# IDC_SMA_Adapter.net
KiCad netlist of a schematic drawn in Altium Designer
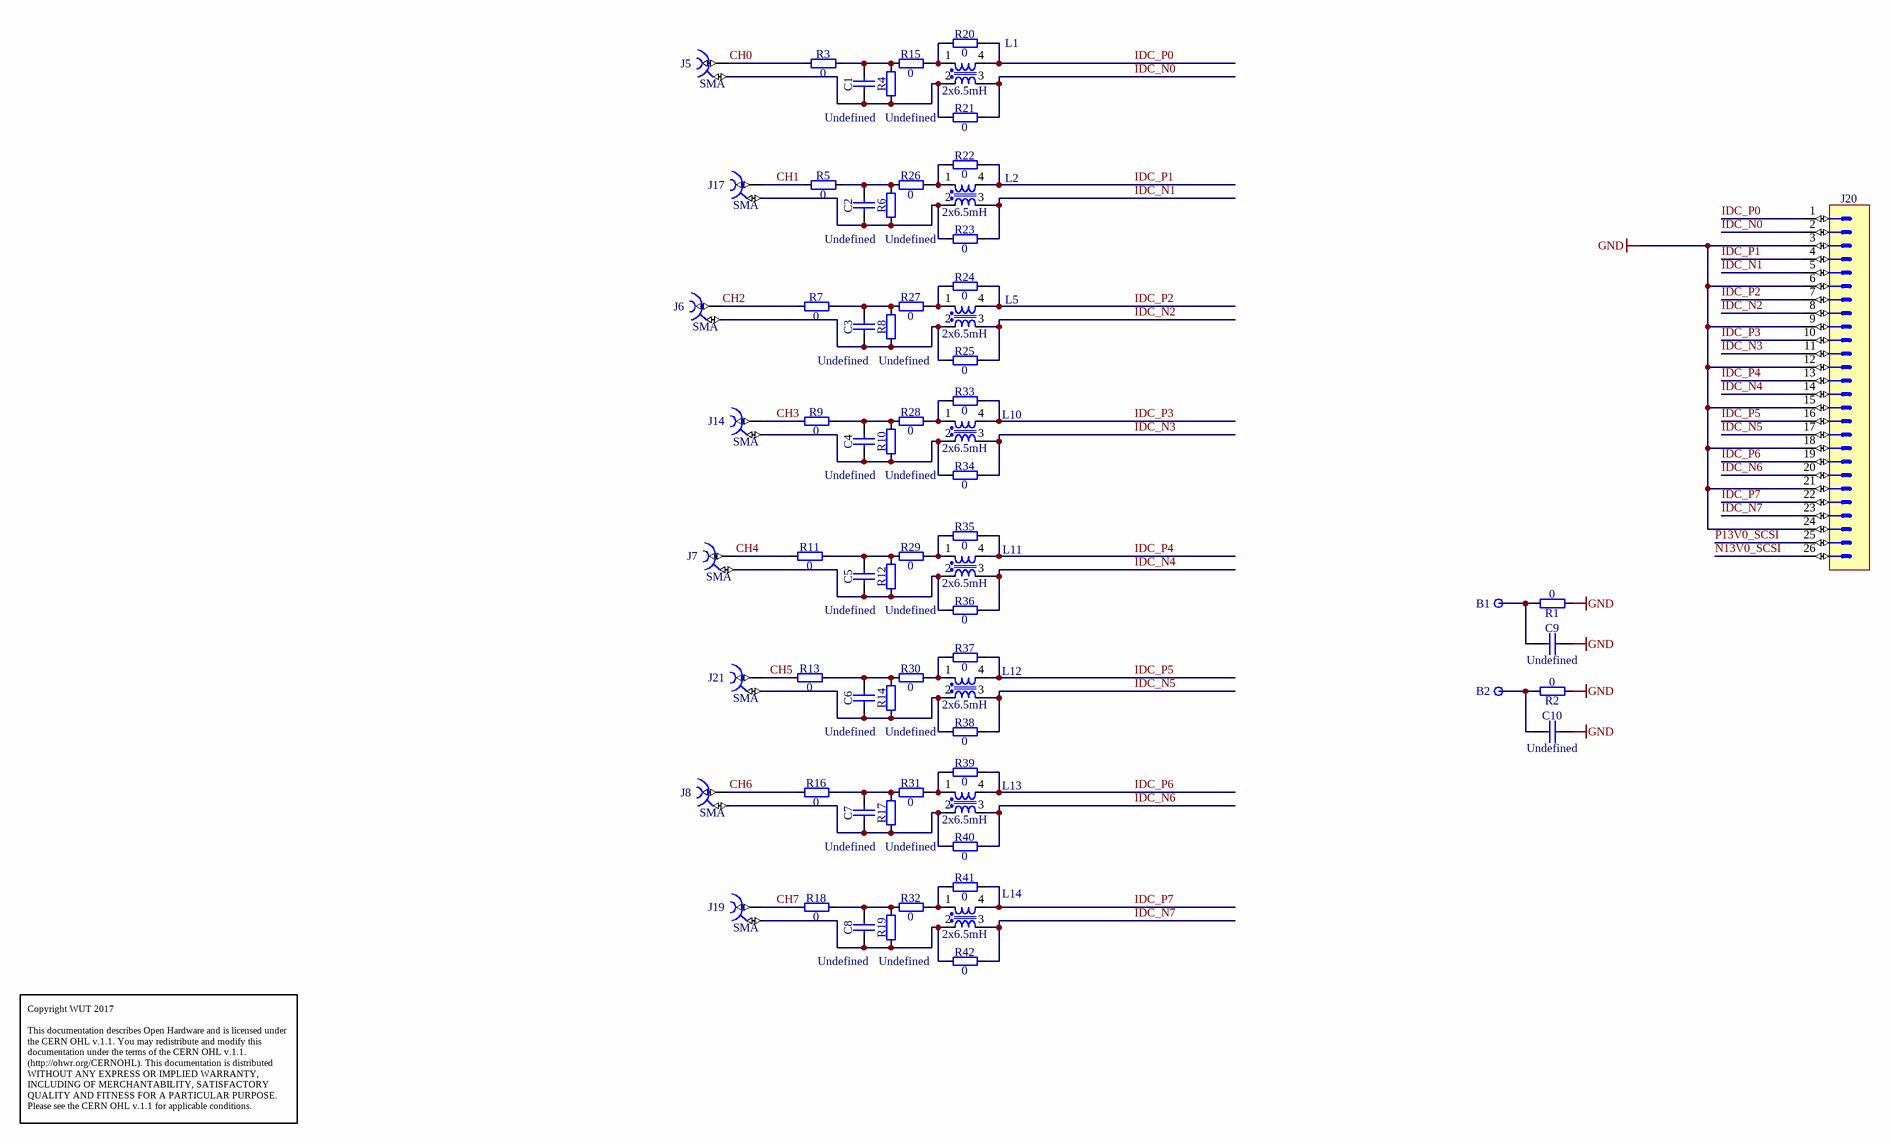
[diagram p0: IDC_SMA_Adapter.SchDoc]

(export (version "E")
  (design (tool "Eeschema 10.0.6"))
  (components
    (comp (ref "B1")
      (value "Plated Hole")
      (footprint "MTG270_500")
      (description "Single Terminal Socket")
      (fields (field (name "PART NUMBER") "PLATED_HOLE2.7_PAD5.0") (field (name "AUTHOR") "CERN DEM JMW"))
      (libsource (lib "Eletro-mechanical") (part "Single Terminal Socket"))
    )
    (comp (ref "B2")
      (value "Plated Hole")
      (footprint "MTG270_500")
      (description "Single Terminal Socket")
      (fields (field (name "PART NUMBER") "PLATED_HOLE2.7_PAD5.0") (field (name "AUTHOR") "CERN DEM JMW"))
      (libsource (lib "Eletro-mechanical") (part "Single Terminal Socket"))
    )
    (comp (ref "C1")
      (value "Undefined")
      (footprint "CAPC2012X135N")
      (description "Non-polarised capacitor")
      (fields (field (name "PART NUMBER") "CC0805_NO-VALUE") (field (name "AUTHOR") "CERN DEM JLC"))
      (libsource (lib "Capacitors") (part "Capacitor - non polarized"))
    )
    (comp (ref "C2")
      (value "Undefined")
      (footprint "CAPC2012X135N")
      (description "Non-polarised capacitor")
      (fields (field (name "PART NUMBER") "CC0805_NO-VALUE") (field (name "AUTHOR") "CERN DEM JLC"))
      (libsource (lib "Capacitors") (part "Capacitor - non polarized"))
    )
    (comp (ref "C3")
      (value "Undefined")
      (footprint "CAPC2012X135N")
      (description "Non-polarised capacitor")
      (fields (field (name "PART NUMBER") "CC0805_NO-VALUE") (field (name "AUTHOR") "CERN DEM JLC"))
      (libsource (lib "Capacitors") (part "Capacitor - non polarized"))
    )
    (comp (ref "C4")
      (value "Undefined")
      (footprint "CAPC2012X135N")
      (description "Non-polarised capacitor")
      (fields (field (name "PART NUMBER") "CC0805_NO-VALUE") (field (name "AUTHOR") "CERN DEM JLC"))
      (libsource (lib "Capacitors") (part "Capacitor - non polarized"))
    )
    (comp (ref "C5")
      (value "Undefined")
      (footprint "CAPC2012X135N")
      (description "Non-polarised capacitor")
      (fields (field (name "PART NUMBER") "CC0805_NO-VALUE") (field (name "AUTHOR") "CERN DEM JLC"))
      (libsource (lib "Capacitors") (part "Capacitor - non polarized"))
    )
    (comp (ref "C6")
      (value "Undefined")
      (footprint "CAPC2012X135N")
      (description "Non-polarised capacitor")
      (fields (field (name "PART NUMBER") "CC0805_NO-VALUE") (field (name "AUTHOR") "CERN DEM JLC"))
      (libsource (lib "Capacitors") (part "Capacitor - non polarized"))
    )
    (comp (ref "C7")
      (value "Undefined")
      (footprint "CAPC2012X135N")
      (description "Non-polarised capacitor")
      (fields (field (name "PART NUMBER") "CC0805_NO-VALUE") (field (name "AUTHOR") "CERN DEM JLC"))
      (libsource (lib "Capacitors") (part "Capacitor - non polarized"))
    )
    (comp (ref "C8")
      (value "Undefined")
      (footprint "CAPC2012X135N")
      (description "Non-polarised capacitor")
      (fields (field (name "PART NUMBER") "CC0805_NO-VALUE") (field (name "AUTHOR") "CERN DEM JLC"))
      (libsource (lib "Capacitors") (part "Capacitor - non polarized"))
    )
    (comp (ref "C9")
      (value "Undefined")
      (footprint "CAPC2012X135N")
      (description "Non-polarised capacitor")
      (fields (field (name "PART NUMBER") "CC0805_NO-VALUE") (field (name "AUTHOR") "CERN DEM JLC"))
      (libsource (lib "Capacitors") (part "Capacitor - non polarized"))
    )
    (comp (ref "C10")
      (value "Undefined")
      (footprint "CAPC2012X135N")
      (description "Non-polarised capacitor")
      (fields (field (name "PART NUMBER") "CC0805_NO-VALUE") (field (name "AUTHOR") "CERN DEM JLC"))
      (libsource (lib "Capacitors") (part "Capacitor - non polarized"))
    )
    (comp (ref "J5")
      (value "SMA")
      (footprint "DELOCK_65848")
      (description "50 Ohm Through Hole SMA Right Angle PCB Jack")
      (fields
        (field (name "PART NUMBER") "DELOCK_65848")
        (field (name "MANUFACTURER") "DELOCK")
        (field (name "AUTHOR") "GK")
      )
      (libsource (lib "Connectors") (part "CON_SMA_DELOCK_65848"))
    )
    (comp (ref "J6")
      (value "SMA")
      (footprint "DELOCK_65848")
      (description "50 Ohm Through Hole SMA Right Angle PCB Jack")
      (fields
        (field (name "PART NUMBER") "DELOCK_65848")
        (field (name "MANUFACTURER") "DELOCK")
        (field (name "AUTHOR") "GK")
      )
      (libsource (lib "Connectors") (part "CON_SMA_DELOCK_65848"))
    )
    (comp (ref "J7")
      (value "SMA")
      (footprint "DELOCK_65848")
      (description "50 Ohm Through Hole SMA Right Angle PCB Jack")
      (fields
        (field (name "PART NUMBER") "DELOCK_65848")
        (field (name "MANUFACTURER") "DELOCK")
        (field (name "AUTHOR") "GK")
      )
      (libsource (lib "Connectors") (part "CON_SMA_DELOCK_65848"))
    )
    (comp (ref "J8")
      (value "SMA")
      (footprint "DELOCK_65848")
      (description "50 Ohm Through Hole SMA Right Angle PCB Jack")
      (fields
        (field (name "PART NUMBER") "DELOCK_65848")
        (field (name "MANUFACTURER") "DELOCK")
        (field (name "AUTHOR") "GK")
      )
      (libsource (lib "Connectors") (part "CON_SMA_DELOCK_65848"))
    )
    (comp (ref "J14")
      (value "SMA")
      (footprint "MOLEX_73251-2120")
      (description "50 Ohm, SMA Edge Mount PCB, With Jam Nut And Lock Washer")
      (fields
        (field (name "PART NUMBER") "MOLEX_73251-2120")
        (field (name "MANUFACTURER") "MOLEX")
        (field (name "AUTHOR") "CERN DEM JLC")
      )
      (libsource (lib "LIBRARY_SCH") (part "CON_SMA_RA_SMD_73251-2120"))
    )
    (comp (ref "J17")
      (value "SMA")
      (footprint "MOLEX_73251-2120")
      (description "50 Ohm, SMA Edge Mount PCB, With Jam Nut And Lock Washer")
      (fields
        (field (name "PART NUMBER") "MOLEX_73251-2120")
        (field (name "MANUFACTURER") "MOLEX")
        (field (name "AUTHOR") "CERN DEM JLC")
      )
      (libsource (lib "LIBRARY_SCH") (part "CON_SMA_RA_SMD_73251-2120"))
    )
    (comp (ref "J19")
      (value "SMA")
      (footprint "MOLEX_73251-2120")
      (description "50 Ohm, SMA Edge Mount PCB, With Jam Nut And Lock Washer")
      (fields
        (field (name "PART NUMBER") "MOLEX_73251-2120")
        (field (name "MANUFACTURER") "MOLEX")
        (field (name "AUTHOR") "CERN DEM JLC")
      )
      (libsource (lib "LIBRARY_SCH") (part "CON_SMA_RA_SMD_73251-2120"))
    )
    (comp (ref "J20")
      (value "Header 26")
      (footprint "3M_N2526-6003RB")
      (description "Connector 26 Male")
      (fields
        (field (name "PART NUMBER") "3M_N2526-6003RB")
        (field (name "MANUFACTURER") "3M")
        (field (name "AUTHOR") "CERN DEM JLC")
      )
      (libsource (lib "Connectors") (part "Connector 26 Male"))
    )
    (comp (ref "J21")
      (value "SMA")
      (footprint "MOLEX_73251-2120")
      (description "50 Ohm, SMA Edge Mount PCB, With Jam Nut And Lock Washer")
      (fields
        (field (name "PART NUMBER") "MOLEX_73251-2120")
        (field (name "MANUFACTURER") "MOLEX")
        (field (name "AUTHOR") "CERN DEM JLC")
      )
      (libsource (lib "LIBRARY_SCH") (part "CON_SMA_RA_SMD_73251-2120"))
    )
    (comp (ref "L1")
      (value "2x6.5mH")
      (footprint "IND_WURTH_WE-SL2")
      (description "Inductor Common Mode")
      (fields
        (field (name "PART NUMBER") "IND_6.5MH_50%_WURTH_WE-SL2-744229")
        (field (name "POWER") "400mA")
        (field (name "AUTHOR") "CERN DEM JLC")
      )
      (libsource (lib "Inductors & Transformers") (part "Inductor Common Mode 1Dot-4 2Dot-3"))
    )
    (comp (ref "L2")
      (value "2x6.5mH")
      (footprint "IND_WURTH_WE-SL2")
      (description "Inductor Common Mode")
      (fields
        (field (name "PART NUMBER") "IND_6.5MH_50%_WURTH_WE-SL2-744229")
        (field (name "POWER") "400mA")
        (field (name "AUTHOR") "CERN DEM JLC")
      )
      (libsource (lib "Inductors & Transformers") (part "Inductor Common Mode 1Dot-4 2Dot-3"))
    )
    (comp (ref "L5")
      (value "2x6.5mH")
      (footprint "IND_WURTH_WE-SL2")
      (description "Inductor Common Mode")
      (fields
        (field (name "PART NUMBER") "IND_6.5MH_50%_WURTH_WE-SL2-744229")
        (field (name "POWER") "400mA")
        (field (name "AUTHOR") "CERN DEM JLC")
      )
      (libsource (lib "Inductors & Transformers") (part "Inductor Common Mode 1Dot-4 2Dot-3"))
    )
    (comp (ref "L10")
      (value "2x6.5mH")
      (footprint "IND_WURTH_WE-SL2")
      (description "Inductor Common Mode")
      (fields
        (field (name "PART NUMBER") "IND_6.5MH_50%_WURTH_WE-SL2-744229")
        (field (name "POWER") "400mA")
        (field (name "AUTHOR") "CERN DEM JLC")
      )
      (libsource (lib "Inductors & Transformers") (part "Inductor Common Mode 1Dot-4 2Dot-3"))
    )
    (comp (ref "L11")
      (value "2x6.5mH")
      (footprint "IND_WURTH_WE-SL2")
      (description "Inductor Common Mode")
      (fields
        (field (name "PART NUMBER") "IND_6.5MH_50%_WURTH_WE-SL2-744229")
        (field (name "POWER") "400mA")
        (field (name "AUTHOR") "CERN DEM JLC")
      )
      (libsource (lib "Inductors & Transformers") (part "Inductor Common Mode 1Dot-4 2Dot-3"))
    )
    (comp (ref "L12")
      (value "2x6.5mH")
      (footprint "IND_WURTH_WE-SL2")
      (description "Inductor Common Mode")
      (fields
        (field (name "PART NUMBER") "IND_6.5MH_50%_WURTH_WE-SL2-744229")
        (field (name "POWER") "400mA")
        (field (name "AUTHOR") "CERN DEM JLC")
      )
      (libsource (lib "Inductors & Transformers") (part "Inductor Common Mode 1Dot-4 2Dot-3"))
    )
    (comp (ref "L13")
      (value "2x6.5mH")
      (footprint "IND_WURTH_WE-SL2")
      (description "Inductor Common Mode")
      (fields
        (field (name "PART NUMBER") "IND_6.5MH_50%_WURTH_WE-SL2-744229")
        (field (name "POWER") "400mA")
        (field (name "AUTHOR") "CERN DEM JLC")
      )
      (libsource (lib "Inductors & Transformers") (part "Inductor Common Mode 1Dot-4 2Dot-3"))
    )
    (comp (ref "L14")
      (value "2x6.5mH")
      (footprint "IND_WURTH_WE-SL2")
      (description "Inductor Common Mode")
      (fields
        (field (name "PART NUMBER") "IND_6.5MH_50%_WURTH_WE-SL2-744229")
        (field (name "POWER") "400mA")
        (field (name "AUTHOR") "CERN DEM JLC")
      )
      (libsource (lib "Inductors & Transformers") (part "Inductor Common Mode 1Dot-4 2Dot-3"))
    )
    (comp (ref "R1")
      (value "0")
      (footprint "RESC1608X55N")
      (description "Resistor")
      (fields
        (field (name "PART NUMBER") "R0603_0R_JUMPER")
        (field (name "MANUFACTURER") "GENERIC")
        (field (name "AUTHOR") "CERN DEM JLC")
      )
      (libsource (lib "Resistors") (part "Resistor"))
    )
    (comp (ref "R2")
      (value "0")
      (footprint "RESC1608X55N")
      (description "Resistor")
      (fields
        (field (name "PART NUMBER") "R0603_0R_JUMPER")
        (field (name "MANUFACTURER") "GENERIC")
        (field (name "AUTHOR") "CERN DEM JLC")
      )
      (libsource (lib "Resistors") (part "Resistor"))
    )
    (comp (ref "R3")
      (value "0")
      (footprint "RESC1608X55N")
      (description "Resistor")
      (fields
        (field (name "PART NUMBER") "R0603_0R_JUMPER")
        (field (name "MANUFACTURER") "GENERIC")
        (field (name "AUTHOR") "CERN DEM JLC")
      )
      (libsource (lib "Resistors") (part "Resistor"))
    )
    (comp (ref "R4")
      (value "Undefined")
      (footprint "RESC1608X55N")
      (description "Resistor")
      (fields (field (name "PART NUMBER") "R0603_NO-VALUE") (field (name "AUTHOR") "CERN DEM JLC"))
      (libsource (lib "Resistors") (part "Resistor"))
    )
    (comp (ref "R5")
      (value "0")
      (footprint "RESC1608X55N")
      (description "Resistor")
      (fields
        (field (name "PART NUMBER") "R0603_0R_JUMPER")
        (field (name "MANUFACTURER") "GENERIC")
        (field (name "AUTHOR") "CERN DEM JLC")
      )
      (libsource (lib "Resistors") (part "Resistor"))
    )
    (comp (ref "R6")
      (value "Undefined")
      (footprint "RESC1608X55N")
      (description "Resistor")
      (fields (field (name "PART NUMBER") "R0603_NO-VALUE") (field (name "AUTHOR") "CERN DEM JLC"))
      (libsource (lib "Resistors") (part "Resistor"))
    )
    (comp (ref "R7")
      (value "0")
      (footprint "RESC1608X55N")
      (description "Resistor")
      (fields
        (field (name "PART NUMBER") "R0603_0R_JUMPER")
        (field (name "MANUFACTURER") "GENERIC")
        (field (name "AUTHOR") "CERN DEM JLC")
      )
      (libsource (lib "Resistors") (part "Resistor"))
    )
    (comp (ref "R8")
      (value "Undefined")
      (footprint "RESC1608X55N")
      (description "Resistor")
      (fields (field (name "PART NUMBER") "R0603_NO-VALUE") (field (name "AUTHOR") "CERN DEM JLC"))
      (libsource (lib "Resistors") (part "Resistor"))
    )
    (comp (ref "R9")
      (value "0")
      (footprint "RESC1608X55N")
      (description "Resistor")
      (fields
        (field (name "PART NUMBER") "R0603_0R_JUMPER")
        (field (name "MANUFACTURER") "GENERIC")
        (field (name "AUTHOR") "CERN DEM JLC")
      )
      (libsource (lib "Resistors") (part "Resistor"))
    )
    (comp (ref "R10")
      (value "Undefined")
      (footprint "RESC1608X55N")
      (description "Resistor")
      (fields (field (name "PART NUMBER") "R0603_NO-VALUE") (field (name "AUTHOR") "CERN DEM JLC"))
      (libsource (lib "Resistors") (part "Resistor"))
    )
    (comp (ref "R11")
      (value "0")
      (footprint "RESC1608X55N")
      (description "Resistor")
      (fields
        (field (name "PART NUMBER") "R0603_0R_JUMPER")
        (field (name "MANUFACTURER") "GENERIC")
        (field (name "AUTHOR") "CERN DEM JLC")
      )
      (libsource (lib "Resistors") (part "Resistor"))
    )
    (comp (ref "R12")
      (value "Undefined")
      (footprint "RESC1608X55N")
      (description "Resistor")
      (fields (field (name "PART NUMBER") "R0603_NO-VALUE") (field (name "AUTHOR") "CERN DEM JLC"))
      (libsource (lib "Resistors") (part "Resistor"))
    )
    (comp (ref "R13")
      (value "0")
      (footprint "RESC1608X55N")
      (description "Resistor")
      (fields
        (field (name "PART NUMBER") "R0603_0R_JUMPER")
        (field (name "MANUFACTURER") "GENERIC")
        (field (name "AUTHOR") "CERN DEM JLC")
      )
      (libsource (lib "Resistors") (part "Resistor"))
    )
    (comp (ref "R14")
      (value "Undefined")
      (footprint "RESC1608X55N")
      (description "Resistor")
      (fields (field (name "PART NUMBER") "R0603_NO-VALUE") (field (name "AUTHOR") "CERN DEM JLC"))
      (libsource (lib "Resistors") (part "Resistor"))
    )
    (comp (ref "R15")
      (value "0")
      (footprint "RESC1608X55N")
      (description "Resistor")
      (fields
        (field (name "PART NUMBER") "R0603_0R_JUMPER")
        (field (name "MANUFACTURER") "GENERIC")
        (field (name "AUTHOR") "CERN DEM JLC")
      )
      (libsource (lib "Resistors") (part "Resistor"))
    )
    (comp (ref "R16")
      (value "0")
      (footprint "RESC1608X55N")
      (description "Resistor")
      (fields
        (field (name "PART NUMBER") "R0603_0R_JUMPER")
        (field (name "MANUFACTURER") "GENERIC")
        (field (name "AUTHOR") "CERN DEM JLC")
      )
      (libsource (lib "Resistors") (part "Resistor"))
    )
    (comp (ref "R17")
      (value "Undefined")
      (footprint "RESC1608X55N")
      (description "Resistor")
      (fields (field (name "PART NUMBER") "R0603_NO-VALUE") (field (name "AUTHOR") "CERN DEM JLC"))
      (libsource (lib "Resistors") (part "Resistor"))
    )
    (comp (ref "R18")
      (value "0")
      (footprint "RESC1608X55N")
      (description "Resistor")
      (fields
        (field (name "PART NUMBER") "R0603_0R_JUMPER")
        (field (name "MANUFACTURER") "GENERIC")
        (field (name "AUTHOR") "CERN DEM JLC")
      )
      (libsource (lib "Resistors") (part "Resistor"))
    )
    (comp (ref "R19")
      (value "Undefined")
      (footprint "RESC1608X55N")
      (description "Resistor")
      (fields (field (name "PART NUMBER") "R0603_NO-VALUE") (field (name "AUTHOR") "CERN DEM JLC"))
      (libsource (lib "Resistors") (part "Resistor"))
    )
    (comp (ref "R20")
      (value "0")
      (footprint "RESC1608X55N")
      (description "Resistor")
      (fields
        (field (name "PART NUMBER") "R0603_0R_JUMPER")
        (field (name "MANUFACTURER") "GENERIC")
        (field (name "AUTHOR") "CERN DEM JLC")
      )
      (libsource (lib "Resistors") (part "Resistor"))
    )
    (comp (ref "R21")
      (value "0")
      (footprint "RESC1608X55N")
      (description "Resistor")
      (fields
        (field (name "PART NUMBER") "R0603_0R_JUMPER")
        (field (name "MANUFACTURER") "GENERIC")
        (field (name "AUTHOR") "CERN DEM JLC")
      )
      (libsource (lib "Resistors") (part "Resistor"))
    )
    (comp (ref "R22")
      (value "0")
      (footprint "RESC1608X55N")
      (description "Resistor")
      (fields
        (field (name "PART NUMBER") "R0603_0R_JUMPER")
        (field (name "MANUFACTURER") "GENERIC")
        (field (name "AUTHOR") "CERN DEM JLC")
      )
      (libsource (lib "Resistors") (part "Resistor"))
    )
    (comp (ref "R23")
      (value "0")
      (footprint "RESC1608X55N")
      (description "Resistor")
      (fields
        (field (name "PART NUMBER") "R0603_0R_JUMPER")
        (field (name "MANUFACTURER") "GENERIC")
        (field (name "AUTHOR") "CERN DEM JLC")
      )
      (libsource (lib "Resistors") (part "Resistor"))
    )
    (comp (ref "R24")
      (value "0")
      (footprint "RESC1608X55N")
      (description "Resistor")
      (fields
        (field (name "PART NUMBER") "R0603_0R_JUMPER")
        (field (name "MANUFACTURER") "GENERIC")
        (field (name "AUTHOR") "CERN DEM JLC")
      )
      (libsource (lib "Resistors") (part "Resistor"))
    )
    (comp (ref "R25")
      (value "0")
      (footprint "RESC1608X55N")
      (description "Resistor")
      (fields
        (field (name "PART NUMBER") "R0603_0R_JUMPER")
        (field (name "MANUFACTURER") "GENERIC")
        (field (name "AUTHOR") "CERN DEM JLC")
      )
      (libsource (lib "Resistors") (part "Resistor"))
    )
    (comp (ref "R26")
      (value "0")
      (footprint "RESC1608X55N")
      (description "Resistor")
      (fields
        (field (name "PART NUMBER") "R0603_0R_JUMPER")
        (field (name "MANUFACTURER") "GENERIC")
        (field (name "AUTHOR") "CERN DEM JLC")
      )
      (libsource (lib "Resistors") (part "Resistor"))
    )
    (comp (ref "R27")
      (value "0")
      (footprint "RESC1608X55N")
      (description "Resistor")
      (fields
        (field (name "PART NUMBER") "R0603_0R_JUMPER")
        (field (name "MANUFACTURER") "GENERIC")
        (field (name "AUTHOR") "CERN DEM JLC")
      )
      (libsource (lib "Resistors") (part "Resistor"))
    )
    (comp (ref "R28")
      (value "0")
      (footprint "RESC1608X55N")
      (description "Resistor")
      (fields
        (field (name "PART NUMBER") "R0603_0R_JUMPER")
        (field (name "MANUFACTURER") "GENERIC")
        (field (name "AUTHOR") "CERN DEM JLC")
      )
      (libsource (lib "Resistors") (part "Resistor"))
    )
    (comp (ref "R29")
      (value "0")
      (footprint "RESC1608X55N")
      (description "Resistor")
      (fields
        (field (name "PART NUMBER") "R0603_0R_JUMPER")
        (field (name "MANUFACTURER") "GENERIC")
        (field (name "AUTHOR") "CERN DEM JLC")
      )
      (libsource (lib "Resistors") (part "Resistor"))
    )
    (comp (ref "R30")
      (value "0")
      (footprint "RESC1608X55N")
      (description "Resistor")
      (fields
        (field (name "PART NUMBER") "R0603_0R_JUMPER")
        (field (name "MANUFACTURER") "GENERIC")
        (field (name "AUTHOR") "CERN DEM JLC")
      )
      (libsource (lib "Resistors") (part "Resistor"))
    )
    (comp (ref "R31")
      (value "0")
      (footprint "RESC1608X55N")
      (description "Resistor")
      (fields
        (field (name "PART NUMBER") "R0603_0R_JUMPER")
        (field (name "MANUFACTURER") "GENERIC")
        (field (name "AUTHOR") "CERN DEM JLC")
      )
      (libsource (lib "Resistors") (part "Resistor"))
    )
    (comp (ref "R32")
      (value "0")
      (footprint "RESC1608X55N")
      (description "Resistor")
      (fields
        (field (name "PART NUMBER") "R0603_0R_JUMPER")
        (field (name "MANUFACTURER") "GENERIC")
        (field (name "AUTHOR") "CERN DEM JLC")
      )
      (libsource (lib "Resistors") (part "Resistor"))
    )
    (comp (ref "R33")
      (value "0")
      (footprint "RESC1608X55N")
      (description "Resistor")
      (fields
        (field (name "PART NUMBER") "R0603_0R_JUMPER")
        (field (name "MANUFACTURER") "GENERIC")
        (field (name "AUTHOR") "CERN DEM JLC")
      )
      (libsource (lib "Resistors") (part "Resistor"))
    )
    (comp (ref "R34")
      (value "0")
      (footprint "RESC1608X55N")
      (description "Resistor")
      (fields
        (field (name "PART NUMBER") "R0603_0R_JUMPER")
        (field (name "MANUFACTURER") "GENERIC")
        (field (name "AUTHOR") "CERN DEM JLC")
      )
      (libsource (lib "Resistors") (part "Resistor"))
    )
    (comp (ref "R35")
      (value "0")
      (footprint "RESC1608X55N")
      (description "Resistor")
      (fields
        (field (name "PART NUMBER") "R0603_0R_JUMPER")
        (field (name "MANUFACTURER") "GENERIC")
        (field (name "AUTHOR") "CERN DEM JLC")
      )
      (libsource (lib "Resistors") (part "Resistor"))
    )
    (comp (ref "R36")
      (value "0")
      (footprint "RESC1608X55N")
      (description "Resistor")
      (fields
        (field (name "PART NUMBER") "R0603_0R_JUMPER")
        (field (name "MANUFACTURER") "GENERIC")
        (field (name "AUTHOR") "CERN DEM JLC")
      )
      (libsource (lib "Resistors") (part "Resistor"))
    )
    (comp (ref "R37")
      (value "0")
      (footprint "RESC1608X55N")
      (description "Resistor")
      (fields
        (field (name "PART NUMBER") "R0603_0R_JUMPER")
        (field (name "MANUFACTURER") "GENERIC")
        (field (name "AUTHOR") "CERN DEM JLC")
      )
      (libsource (lib "Resistors") (part "Resistor"))
    )
    (comp (ref "R38")
      (value "0")
      (footprint "RESC1608X55N")
      (description "Resistor")
      (fields
        (field (name "PART NUMBER") "R0603_0R_JUMPER")
        (field (name "MANUFACTURER") "GENERIC")
        (field (name "AUTHOR") "CERN DEM JLC")
      )
      (libsource (lib "Resistors") (part "Resistor"))
    )
    (comp (ref "R39")
      (value "0")
      (footprint "RESC1608X55N")
      (description "Resistor")
      (fields
        (field (name "PART NUMBER") "R0603_0R_JUMPER")
        (field (name "MANUFACTURER") "GENERIC")
        (field (name "AUTHOR") "CERN DEM JLC")
      )
      (libsource (lib "Resistors") (part "Resistor"))
    )
    (comp (ref "R40")
      (value "0")
      (footprint "RESC1608X55N")
      (description "Resistor")
      (fields
        (field (name "PART NUMBER") "R0603_0R_JUMPER")
        (field (name "MANUFACTURER") "GENERIC")
        (field (name "AUTHOR") "CERN DEM JLC")
      )
      (libsource (lib "Resistors") (part "Resistor"))
    )
    (comp (ref "R41")
      (value "0")
      (footprint "RESC1608X55N")
      (description "Resistor")
      (fields
        (field (name "PART NUMBER") "R0603_0R_JUMPER")
        (field (name "MANUFACTURER") "GENERIC")
        (field (name "AUTHOR") "CERN DEM JLC")
      )
      (libsource (lib "Resistors") (part "Resistor"))
    )
    (comp (ref "R42")
      (value "0")
      (footprint "RESC1608X55N")
      (description "Resistor")
      (fields
        (field (name "PART NUMBER") "R0603_0R_JUMPER")
        (field (name "MANUFACTURER") "GENERIC")
        (field (name "AUTHOR") "CERN DEM JLC")
      )
      (libsource (lib "Resistors") (part "Resistor"))
    )
  )
  (nets
    (net (code "1") (name "/CH0") (class "Default")
      (node (ref "J5") (pin "1") (pinfunction "1_1") (pintype "bidirectional"))
      (node (ref "R3") (pin "1") (pinfunction "1_1") (pintype "passive"))
    )
    (net (code "2") (name "/CH1") (class "Default")
      (node (ref "J17") (pin "1") (pinfunction "1_1") (pintype "bidirectional"))
      (node (ref "R5") (pin "1") (pinfunction "1_1") (pintype "passive"))
    )
    (net (code "3") (name "/CH2") (class "Default")
      (node (ref "J6") (pin "1") (pinfunction "1_1") (pintype "bidirectional"))
      (node (ref "R7") (pin "1") (pinfunction "1_1") (pintype "passive"))
    )
    (net (code "4") (name "/CH3") (class "Default")
      (node (ref "J14") (pin "1") (pinfunction "1_1") (pintype "bidirectional"))
      (node (ref "R9") (pin "1") (pinfunction "1_1") (pintype "passive"))
    )
    (net (code "5") (name "/CH4") (class "Default")
      (node (ref "J7") (pin "1") (pinfunction "1_1") (pintype "bidirectional"))
      (node (ref "R11") (pin "1") (pinfunction "1_1") (pintype "passive"))
    )
    (net (code "6") (name "/CH5") (class "Default")
      (node (ref "J21") (pin "1") (pinfunction "1_1") (pintype "bidirectional"))
      (node (ref "R13") (pin "1") (pinfunction "1_1") (pintype "passive"))
    )
    (net (code "7") (name "/CH6") (class "Default")
      (node (ref "J8") (pin "1") (pinfunction "1_1") (pintype "bidirectional"))
      (node (ref "R16") (pin "1") (pinfunction "1_1") (pintype "passive"))
    )
    (net (code "8") (name "/CH7") (class "Default")
      (node (ref "J19") (pin "1") (pinfunction "1_1") (pintype "bidirectional"))
      (node (ref "R18") (pin "1") (pinfunction "1_1") (pintype "passive"))
    )
    (net (code "9") (name "/IDC_N0") (class "Default")
      (node (ref "J20") (pin "2") (pinfunction "2_2") (pintype "bidirectional"))
      (node (ref "L1") (pin "3") (pinfunction "3_3") (pintype "passive"))
      (node (ref "R21") (pin "2") (pinfunction "2_2") (pintype "passive"))
    )
    (net (code "10") (name "/IDC_N1") (class "Default")
      (node (ref "J20") (pin "5") (pinfunction "5_5") (pintype "bidirectional"))
      (node (ref "L2") (pin "3") (pinfunction "3_3") (pintype "passive"))
      (node (ref "R23") (pin "2") (pinfunction "2_2") (pintype "passive"))
    )
    (net (code "11") (name "/IDC_N2") (class "Default")
      (node (ref "J20") (pin "8") (pinfunction "8_8") (pintype "bidirectional"))
      (node (ref "L5") (pin "3") (pinfunction "3_3") (pintype "passive"))
      (node (ref "R25") (pin "2") (pinfunction "2_2") (pintype "passive"))
    )
    (net (code "12") (name "/IDC_N3") (class "Default")
      (node (ref "J20") (pin "11") (pinfunction "11_11") (pintype "bidirectional"))
      (node (ref "L10") (pin "3") (pinfunction "3_3") (pintype "passive"))
      (node (ref "R34") (pin "2") (pinfunction "2_2") (pintype "passive"))
    )
    (net (code "13") (name "/IDC_N4") (class "Default")
      (node (ref "J20") (pin "14") (pinfunction "14_14") (pintype "bidirectional"))
      (node (ref "L11") (pin "3") (pinfunction "3_3") (pintype "passive"))
      (node (ref "R36") (pin "2") (pinfunction "2_2") (pintype "passive"))
    )
    (net (code "14") (name "/IDC_N5") (class "Default")
      (node (ref "J20") (pin "17") (pinfunction "17_17") (pintype "bidirectional"))
      (node (ref "L12") (pin "3") (pinfunction "3_3") (pintype "passive"))
      (node (ref "R38") (pin "2") (pinfunction "2_2") (pintype "passive"))
    )
    (net (code "15") (name "/IDC_N6") (class "Default")
      (node (ref "J20") (pin "20") (pinfunction "20_20") (pintype "bidirectional"))
      (node (ref "L13") (pin "3") (pinfunction "3_3") (pintype "passive"))
      (node (ref "R40") (pin "2") (pinfunction "2_2") (pintype "passive"))
    )
    (net (code "16") (name "/IDC_N7") (class "Default")
      (node (ref "J20") (pin "23") (pinfunction "23_23") (pintype "bidirectional"))
      (node (ref "L14") (pin "3") (pinfunction "3_3") (pintype "passive"))
      (node (ref "R42") (pin "2") (pinfunction "2_2") (pintype "passive"))
    )
    (net (code "17") (name "/IDC_P0") (class "Default")
      (node (ref "J20") (pin "1") (pinfunction "1_1") (pintype "bidirectional"))
      (node (ref "L1") (pin "4") (pinfunction "4_4") (pintype "passive"))
      (node (ref "R20") (pin "2") (pinfunction "2_2") (pintype "passive"))
    )
    (net (code "18") (name "/IDC_P1") (class "Default")
      (node (ref "J20") (pin "4") (pinfunction "4_4") (pintype "bidirectional"))
      (node (ref "L2") (pin "4") (pinfunction "4_4") (pintype "passive"))
      (node (ref "R22") (pin "2") (pinfunction "2_2") (pintype "passive"))
    )
    (net (code "19") (name "/IDC_P2") (class "Default")
      (node (ref "J20") (pin "7") (pinfunction "7_7") (pintype "bidirectional"))
      (node (ref "L5") (pin "4") (pinfunction "4_4") (pintype "passive"))
      (node (ref "R24") (pin "2") (pinfunction "2_2") (pintype "passive"))
    )
    (net (code "20") (name "/IDC_P3") (class "Default")
      (node (ref "J20") (pin "10") (pinfunction "10_10") (pintype "bidirectional"))
      (node (ref "L10") (pin "4") (pinfunction "4_4") (pintype "passive"))
      (node (ref "R33") (pin "2") (pinfunction "2_2") (pintype "passive"))
    )
    (net (code "21") (name "/IDC_P4") (class "Default")
      (node (ref "J20") (pin "13") (pinfunction "13_13") (pintype "bidirectional"))
      (node (ref "L11") (pin "4") (pinfunction "4_4") (pintype "passive"))
      (node (ref "R35") (pin "2") (pinfunction "2_2") (pintype "passive"))
    )
    (net (code "22") (name "/IDC_P5") (class "Default")
      (node (ref "J20") (pin "16") (pinfunction "16_16") (pintype "bidirectional"))
      (node (ref "L12") (pin "4") (pinfunction "4_4") (pintype "passive"))
      (node (ref "R37") (pin "2") (pinfunction "2_2") (pintype "passive"))
    )
    (net (code "23") (name "/IDC_P6") (class "Default")
      (node (ref "J20") (pin "19") (pinfunction "19_19") (pintype "bidirectional"))
      (node (ref "L13") (pin "4") (pinfunction "4_4") (pintype "passive"))
      (node (ref "R39") (pin "2") (pinfunction "2_2") (pintype "passive"))
    )
    (net (code "24") (name "/IDC_P7") (class "Default")
      (node (ref "J20") (pin "22") (pinfunction "22_22") (pintype "bidirectional"))
      (node (ref "L14") (pin "4") (pinfunction "4_4") (pintype "passive"))
      (node (ref "R41") (pin "2") (pinfunction "2_2") (pintype "passive"))
    )
    (net (code "25") (name "/N13V0_SCSI") (class "Default")
      (node (ref "J20") (pin "26") (pinfunction "26_26") (pintype "bidirectional"))
    )
    (net (code "26") (name "/P13V0_SCSI") (class "Default")
      (node (ref "J20") (pin "25") (pinfunction "25_25") (pintype "bidirectional"))
    )
    (net (code "27") (name "GND") (class "Default")
      (node (ref "C10") (pin "2") (pinfunction "2_2") (pintype "passive"))
      (node (ref "C9") (pin "2") (pinfunction "2_2") (pintype "passive"))
      (node (ref "J20") (pin "12") (pinfunction "12_12") (pintype "bidirectional"))
      (node (ref "J20") (pin "15") (pinfunction "15_15") (pintype "bidirectional"))
      (node (ref "J20") (pin "18") (pinfunction "18_18") (pintype "bidirectional"))
      (node (ref "J20") (pin "21") (pinfunction "21_21") (pintype "bidirectional"))
      (node (ref "J20") (pin "24") (pinfunction "24_24") (pintype "bidirectional"))
      (node (ref "J20") (pin "3") (pinfunction "3_3") (pintype "bidirectional"))
      (node (ref "J20") (pin "6") (pinfunction "6_6") (pintype "bidirectional"))
      (node (ref "J20") (pin "9") (pinfunction "9_9") (pintype "bidirectional"))
      (node (ref "R1") (pin "1") (pinfunction "1_1") (pintype "passive"))
      (node (ref "R2") (pin "1") (pinfunction "1_1") (pintype "passive"))
    )
    (net (code "28") (name "Net-(B1-Pad1)") (class "Default")
      (node (ref "B1") (pin "1") (pinfunction "1_1") (pintype "bidirectional"))
      (node (ref "C9") (pin "1") (pinfunction "1_1") (pintype "passive"))
      (node (ref "R1") (pin "2") (pinfunction "2_2") (pintype "passive"))
    )
    (net (code "29") (name "Net-(B2-Pad1)") (class "Default")
      (node (ref "B2") (pin "1") (pinfunction "1_1") (pintype "bidirectional"))
      (node (ref "C10") (pin "1") (pinfunction "1_1") (pintype "passive"))
      (node (ref "R2") (pin "2") (pinfunction "2_2") (pintype "passive"))
    )
    (net (code "30") (name "Net-(C1-Pad1)") (class "Default")
      (node (ref "C1") (pin "1") (pinfunction "1_1") (pintype "passive"))
      (node (ref "J5") (pin "2") (pinfunction "2_2") (pintype "bidirectional"))
      (node (ref "L1") (pin "2") (pinfunction "2_2") (pintype "passive"))
      (node (ref "R21") (pin "1") (pinfunction "1_1") (pintype "passive"))
      (node (ref "R4") (pin "1") (pinfunction "1_1") (pintype "passive"))
    )
    (net (code "31") (name "Net-(C1-Pad2)") (class "Default")
      (node (ref "C1") (pin "2") (pinfunction "2_2") (pintype "passive"))
      (node (ref "R15") (pin "1") (pinfunction "1_1") (pintype "passive"))
      (node (ref "R3") (pin "2") (pinfunction "2_2") (pintype "passive"))
      (node (ref "R4") (pin "2") (pinfunction "2_2") (pintype "passive"))
    )
    (net (code "32") (name "Net-(C2-Pad1)") (class "Default")
      (node (ref "C2") (pin "1") (pinfunction "1_1") (pintype "passive"))
      (node (ref "J17") (pin "2") (pinfunction "2_2") (pintype "bidirectional"))
      (node (ref "L2") (pin "2") (pinfunction "2_2") (pintype "passive"))
      (node (ref "R23") (pin "1") (pinfunction "1_1") (pintype "passive"))
      (node (ref "R6") (pin "1") (pinfunction "1_1") (pintype "passive"))
    )
    (net (code "33") (name "Net-(C2-Pad2)") (class "Default")
      (node (ref "C2") (pin "2") (pinfunction "2_2") (pintype "passive"))
      (node (ref "R26") (pin "1") (pinfunction "1_1") (pintype "passive"))
      (node (ref "R5") (pin "2") (pinfunction "2_2") (pintype "passive"))
      (node (ref "R6") (pin "2") (pinfunction "2_2") (pintype "passive"))
    )
    (net (code "34") (name "Net-(C3-Pad1)") (class "Default")
      (node (ref "C3") (pin "1") (pinfunction "1_1") (pintype "passive"))
      (node (ref "J6") (pin "2") (pinfunction "2_2") (pintype "bidirectional"))
      (node (ref "L5") (pin "2") (pinfunction "2_2") (pintype "passive"))
      (node (ref "R25") (pin "1") (pinfunction "1_1") (pintype "passive"))
      (node (ref "R8") (pin "1") (pinfunction "1_1") (pintype "passive"))
    )
    (net (code "35") (name "Net-(C3-Pad2)") (class "Default")
      (node (ref "C3") (pin "2") (pinfunction "2_2") (pintype "passive"))
      (node (ref "R27") (pin "1") (pinfunction "1_1") (pintype "passive"))
      (node (ref "R7") (pin "2") (pinfunction "2_2") (pintype "passive"))
      (node (ref "R8") (pin "2") (pinfunction "2_2") (pintype "passive"))
    )
    (net (code "36") (name "Net-(C4-Pad1)") (class "Default")
      (node (ref "C4") (pin "1") (pinfunction "1_1") (pintype "passive"))
      (node (ref "J14") (pin "2") (pinfunction "2_2") (pintype "bidirectional"))
      (node (ref "L10") (pin "2") (pinfunction "2_2") (pintype "passive"))
      (node (ref "R10") (pin "1") (pinfunction "1_1") (pintype "passive"))
      (node (ref "R34") (pin "1") (pinfunction "1_1") (pintype "passive"))
    )
    (net (code "37") (name "Net-(C4-Pad2)") (class "Default")
      (node (ref "C4") (pin "2") (pinfunction "2_2") (pintype "passive"))
      (node (ref "R10") (pin "2") (pinfunction "2_2") (pintype "passive"))
      (node (ref "R28") (pin "1") (pinfunction "1_1") (pintype "passive"))
      (node (ref "R9") (pin "2") (pinfunction "2_2") (pintype "passive"))
    )
    (net (code "38") (name "Net-(C5-Pad1)") (class "Default")
      (node (ref "C5") (pin "1") (pinfunction "1_1") (pintype "passive"))
      (node (ref "J7") (pin "2") (pinfunction "2_2") (pintype "bidirectional"))
      (node (ref "L11") (pin "2") (pinfunction "2_2") (pintype "passive"))
      (node (ref "R12") (pin "1") (pinfunction "1_1") (pintype "passive"))
      (node (ref "R36") (pin "1") (pinfunction "1_1") (pintype "passive"))
    )
    (net (code "39") (name "Net-(C5-Pad2)") (class "Default")
      (node (ref "C5") (pin "2") (pinfunction "2_2") (pintype "passive"))
      (node (ref "R11") (pin "2") (pinfunction "2_2") (pintype "passive"))
      (node (ref "R12") (pin "2") (pinfunction "2_2") (pintype "passive"))
      (node (ref "R29") (pin "1") (pinfunction "1_1") (pintype "passive"))
    )
    (net (code "40") (name "Net-(C6-Pad1)") (class "Default")
      (node (ref "C6") (pin "1") (pinfunction "1_1") (pintype "passive"))
      (node (ref "J21") (pin "2") (pinfunction "2_2") (pintype "bidirectional"))
      (node (ref "L12") (pin "2") (pinfunction "2_2") (pintype "passive"))
      (node (ref "R14") (pin "1") (pinfunction "1_1") (pintype "passive"))
      (node (ref "R38") (pin "1") (pinfunction "1_1") (pintype "passive"))
    )
    (net (code "41") (name "Net-(C6-Pad2)") (class "Default")
      (node (ref "C6") (pin "2") (pinfunction "2_2") (pintype "passive"))
      (node (ref "R13") (pin "2") (pinfunction "2_2") (pintype "passive"))
      (node (ref "R14") (pin "2") (pinfunction "2_2") (pintype "passive"))
      (node (ref "R30") (pin "1") (pinfunction "1_1") (pintype "passive"))
    )
    (net (code "42") (name "Net-(C7-Pad1)") (class "Default")
      (node (ref "C7") (pin "1") (pinfunction "1_1") (pintype "passive"))
      (node (ref "J8") (pin "2") (pinfunction "2_2") (pintype "bidirectional"))
      (node (ref "L13") (pin "2") (pinfunction "2_2") (pintype "passive"))
      (node (ref "R17") (pin "1") (pinfunction "1_1") (pintype "passive"))
      (node (ref "R40") (pin "1") (pinfunction "1_1") (pintype "passive"))
    )
    (net (code "43") (name "Net-(C7-Pad2)") (class "Default")
      (node (ref "C7") (pin "2") (pinfunction "2_2") (pintype "passive"))
      (node (ref "R16") (pin "2") (pinfunction "2_2") (pintype "passive"))
      (node (ref "R17") (pin "2") (pinfunction "2_2") (pintype "passive"))
      (node (ref "R31") (pin "1") (pinfunction "1_1") (pintype "passive"))
    )
    (net (code "44") (name "Net-(C8-Pad1)") (class "Default")
      (node (ref "C8") (pin "1") (pinfunction "1_1") (pintype "passive"))
      (node (ref "J19") (pin "2") (pinfunction "2_2") (pintype "bidirectional"))
      (node (ref "L14") (pin "2") (pinfunction "2_2") (pintype "passive"))
      (node (ref "R19") (pin "1") (pinfunction "1_1") (pintype "passive"))
      (node (ref "R42") (pin "1") (pinfunction "1_1") (pintype "passive"))
    )
    (net (code "45") (name "Net-(C8-Pad2)") (class "Default")
      (node (ref "C8") (pin "2") (pinfunction "2_2") (pintype "passive"))
      (node (ref "R18") (pin "2") (pinfunction "2_2") (pintype "passive"))
      (node (ref "R19") (pin "2") (pinfunction "2_2") (pintype "passive"))
      (node (ref "R32") (pin "1") (pinfunction "1_1") (pintype "passive"))
    )
    (net (code "46") (name "Net-(L1-Pad1)") (class "Default")
      (node (ref "L1") (pin "1") (pinfunction "1_1") (pintype "passive"))
      (node (ref "R15") (pin "2") (pinfunction "2_2") (pintype "passive"))
      (node (ref "R20") (pin "1") (pinfunction "1_1") (pintype "passive"))
    )
    (net (code "47") (name "Net-(L2-Pad1)") (class "Default")
      (node (ref "L2") (pin "1") (pinfunction "1_1") (pintype "passive"))
      (node (ref "R22") (pin "1") (pinfunction "1_1") (pintype "passive"))
      (node (ref "R26") (pin "2") (pinfunction "2_2") (pintype "passive"))
    )
    (net (code "48") (name "Net-(L5-Pad1)") (class "Default")
      (node (ref "L5") (pin "1") (pinfunction "1_1") (pintype "passive"))
      (node (ref "R24") (pin "1") (pinfunction "1_1") (pintype "passive"))
      (node (ref "R27") (pin "2") (pinfunction "2_2") (pintype "passive"))
    )
    (net (code "49") (name "Net-(L10-Pad1)") (class "Default")
      (node (ref "L10") (pin "1") (pinfunction "1_1") (pintype "passive"))
      (node (ref "R28") (pin "2") (pinfunction "2_2") (pintype "passive"))
      (node (ref "R33") (pin "1") (pinfunction "1_1") (pintype "passive"))
    )
    (net (code "50") (name "Net-(L11-Pad1)") (class "Default")
      (node (ref "L11") (pin "1") (pinfunction "1_1") (pintype "passive"))
      (node (ref "R29") (pin "2") (pinfunction "2_2") (pintype "passive"))
      (node (ref "R35") (pin "1") (pinfunction "1_1") (pintype "passive"))
    )
    (net (code "51") (name "Net-(L12-Pad1)") (class "Default")
      (node (ref "L12") (pin "1") (pinfunction "1_1") (pintype "passive"))
      (node (ref "R30") (pin "2") (pinfunction "2_2") (pintype "passive"))
      (node (ref "R37") (pin "1") (pinfunction "1_1") (pintype "passive"))
    )
    (net (code "52") (name "Net-(L13-Pad1)") (class "Default")
      (node (ref "L13") (pin "1") (pinfunction "1_1") (pintype "passive"))
      (node (ref "R31") (pin "2") (pinfunction "2_2") (pintype "passive"))
      (node (ref "R39") (pin "1") (pinfunction "1_1") (pintype "passive"))
    )
    (net (code "53") (name "Net-(L14-Pad1)") (class "Default")
      (node (ref "L14") (pin "1") (pinfunction "1_1") (pintype "passive"))
      (node (ref "R32") (pin "2") (pinfunction "2_2") (pintype "passive"))
      (node (ref "R41") (pin "1") (pinfunction "1_1") (pintype "passive"))
    )
  )
)
